# NeoGeo_JAMMA_OD.net
KiCad netlist of a schematic drawn in EAGLE
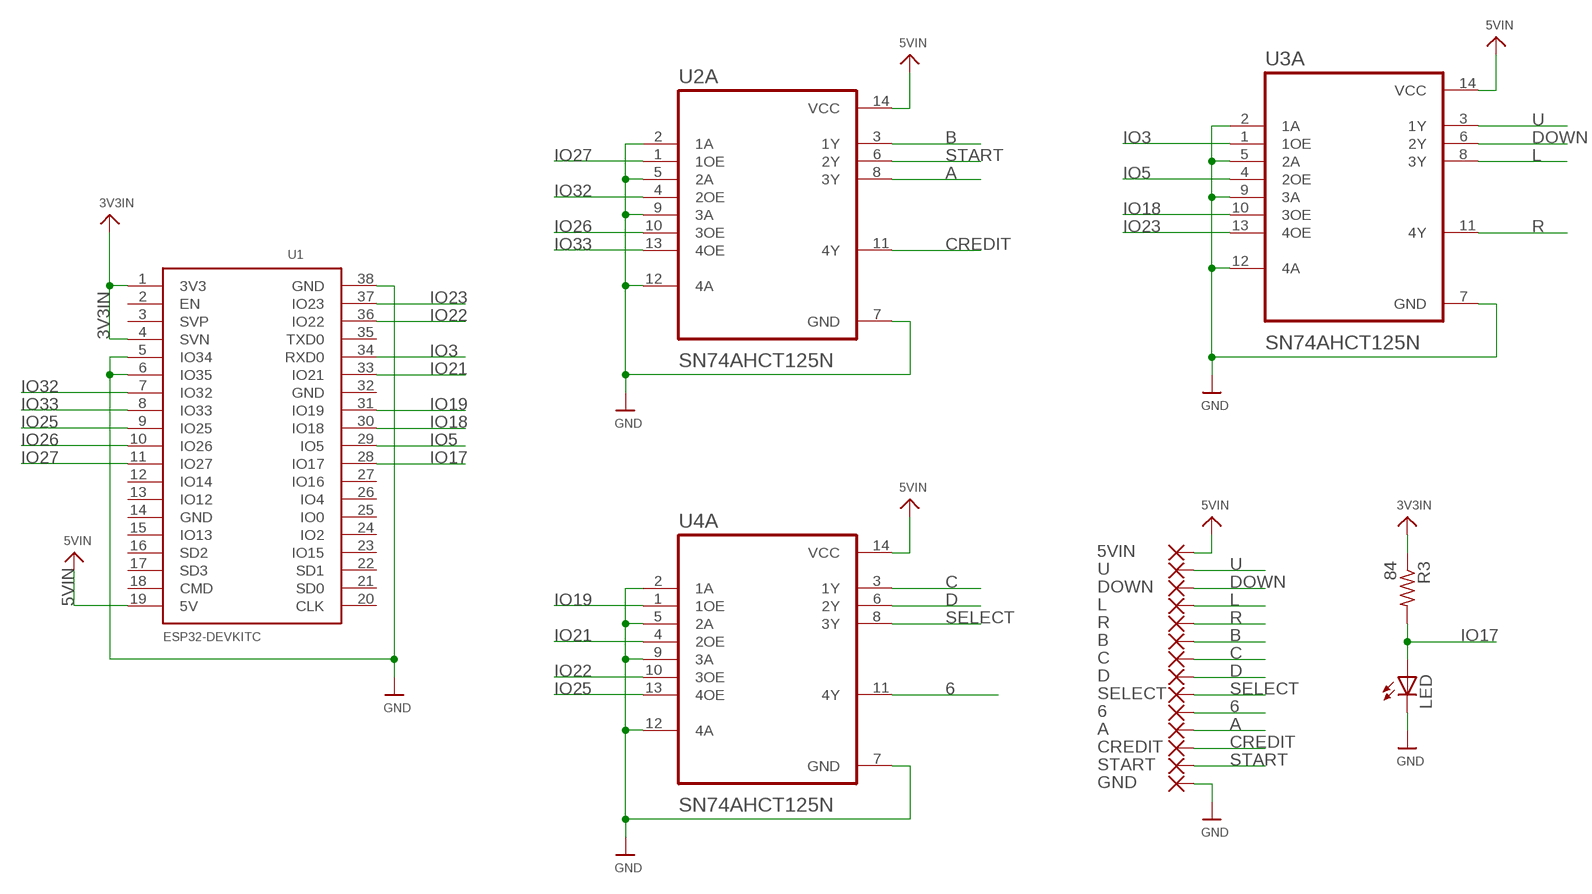
[diagram p0: schematic, sheet 1]

(export (version "E")
  (design (tool "Eeschema 10.0.6"))
  (components
    (comp (ref "5VIN")
      (value "SMD5")
      (footprint "eagle-import:SMD2,54-5,08")
      (libsource (lib "eagle-import") (part "SMD5"))
    )
    (comp (ref "6")
      (value "SMD5")
      (footprint "eagle-import:SMD2,54-5,08")
      (libsource (lib "eagle-import") (part "SMD5"))
    )
    (comp (ref "A")
      (value "SMD5")
      (footprint "eagle-import:SMD2,54-5,08")
      (libsource (lib "eagle-import") (part "SMD5"))
    )
    (comp (ref "B")
      (value "SMD5")
      (footprint "eagle-import:SMD2,54-5,08")
      (libsource (lib "eagle-import") (part "SMD5"))
    )
    (comp (ref "C")
      (value "SMD5")
      (footprint "eagle-import:SMD2,54-5,08")
      (libsource (lib "eagle-import") (part "SMD5"))
    )
    (comp (ref "CREDIT")
      (value "SMD5")
      (footprint "eagle-import:SMD2,54-5,08")
      (libsource (lib "eagle-import") (part "SMD5"))
    )
    (comp (ref "D")
      (value "SMD5")
      (footprint "eagle-import:SMD2,54-5,08")
      (libsource (lib "eagle-import") (part "SMD5"))
    )
    (comp (ref "DOWN")
      (value "SMD5")
      (footprint "eagle-import:SMD2,54-5,08")
      (libsource (lib "eagle-import") (part "SMD5"))
    )
    (comp (ref "GND")
      (value "SMD5")
      (footprint "eagle-import:SMD2,54-5,08")
      (libsource (lib "eagle-import") (part "SMD5"))
    )
    (comp (ref "L")
      (value "SMD5")
      (footprint "eagle-import:SMD2,54-5,08")
      (libsource (lib "eagle-import") (part "SMD5"))
    )
    (comp (ref "LED")
      (value "LEDCHIPLED_1206")
      (footprint "eagle-import:CHIPLED_1206")
      (libsource (lib "eagle-import") (part "LEDCHIPLED_1206"))
    )
    (comp (ref "R")
      (value "SMD5")
      (footprint "eagle-import:SMD2,54-5,08")
      (libsource (lib "eagle-import") (part "SMD5"))
    )
    (comp (ref "R3")
      (value "84")
      (footprint "eagle-import:R1206")
      (libsource (lib "eagle-import") (part "R-US_R1206"))
    )
    (comp (ref "SELECT")
      (value "SMD5")
      (footprint "eagle-import:SMD2,54-5,08")
      (libsource (lib "eagle-import") (part "SMD5"))
    )
    (comp (ref "START")
      (value "SMD5")
      (footprint "eagle-import:SMD2,54-5,08")
      (libsource (lib "eagle-import") (part "SMD5"))
    )
    (comp (ref "U")
      (value "SMD5")
      (footprint "eagle-import:SMD2,54-5,08")
      (libsource (lib "eagle-import") (part "SMD5"))
    )
    (comp (ref "U1")
      (value "ESP32DEVKITC")
      (footprint "eagle-import:ESP32-DEVKITC")
      (libsource (lib "eagle-import") (part "ESP32DEVKITC"))
    )
    (comp (ref "U2A")
      (value "SN74AHCT125N")
      (footprint "eagle-import:DIP794W45P254L1969H508Q14")
      (fields (field (name "MF") "Texas Instruments"))
      (libsource (lib "eagle-import") (part "SN74AHCT125N"))
    )
    (comp (ref "U3A")
      (value "SN74AHCT125N")
      (footprint "eagle-import:DIP794W45P254L1969H508Q14")
      (fields (field (name "MF") "Texas Instruments"))
      (libsource (lib "eagle-import") (part "SN74AHCT125N"))
    )
    (comp (ref "U4A")
      (value "SN74AHCT125N")
      (footprint "eagle-import:DIP794W45P254L1969H508Q14")
      (fields (field (name "MF") "Texas Instruments"))
      (libsource (lib "eagle-import") (part "SN74AHCT125N"))
    )
  )
  (nets
    (net (code "1") (name "/6") (class "Default")
      (node (ref "6") (pin "1") (pinfunction "P_1") (pintype "passive"))
      (node (ref "U4A") (pin "11") (pinfunction "4Y_11") (pintype "output"))
    )
    (net (code "2") (name "/A") (class "Default")
      (node (ref "A") (pin "1") (pinfunction "P_1") (pintype "passive"))
      (node (ref "U2A") (pin "8") (pinfunction "3Y_8") (pintype "output"))
    )
    (net (code "3") (name "/B") (class "Default")
      (node (ref "B") (pin "1") (pinfunction "P_1") (pintype "passive"))
      (node (ref "U2A") (pin "3") (pinfunction "1Y_3") (pintype "output"))
    )
    (net (code "4") (name "/C") (class "Default")
      (node (ref "C") (pin "1") (pinfunction "P_1") (pintype "passive"))
      (node (ref "U4A") (pin "3") (pinfunction "1Y_3") (pintype "output"))
    )
    (net (code "5") (name "/CREDIT") (class "Default")
      (node (ref "CREDIT") (pin "1") (pinfunction "P_1") (pintype "passive"))
      (node (ref "U2A") (pin "11") (pinfunction "4Y_11") (pintype "output"))
    )
    (net (code "6") (name "/D") (class "Default")
      (node (ref "D") (pin "1") (pinfunction "P_1") (pintype "passive"))
      (node (ref "U4A") (pin "6") (pinfunction "2Y_6") (pintype "output"))
    )
    (net (code "7") (name "/DOWN") (class "Default")
      (node (ref "DOWN") (pin "1") (pinfunction "P_1") (pintype "passive"))
      (node (ref "U3A") (pin "6") (pinfunction "2Y_6") (pintype "output"))
    )
    (net (code "8") (name "/IO3") (class "Default")
      (node (ref "U1") (pin "34") (pinfunction "RXD0_34") (pintype "bidirectional"))
      (node (ref "U3A") (pin "1") (pinfunction "1OE_1") (pintype "input"))
    )
    (net (code "9") (name "/IO5") (class "Default")
      (node (ref "U1") (pin "29") (pinfunction "IO5_29") (pintype "bidirectional"))
      (node (ref "U3A") (pin "4") (pinfunction "2OE_4") (pintype "input"))
    )
    (net (code "10") (name "/IO17") (class "Default")
      (node (ref "LED") (pin "A") (pinfunction "A_A") (pintype "passive"))
      (node (ref "R3") (pin "2") (pinfunction "2_2") (pintype "passive"))
      (node (ref "U1") (pin "28") (pinfunction "IO17_28") (pintype "bidirectional"))
    )
    (net (code "11") (name "/IO18") (class "Default")
      (node (ref "U1") (pin "30") (pinfunction "IO18_30") (pintype "bidirectional"))
      (node (ref "U3A") (pin "10") (pinfunction "3OE_10") (pintype "input"))
    )
    (net (code "12") (name "/IO19") (class "Default")
      (node (ref "U1") (pin "31") (pinfunction "IO19_31") (pintype "bidirectional"))
      (node (ref "U4A") (pin "1") (pinfunction "1OE_1") (pintype "input"))
    )
    (net (code "13") (name "/IO21") (class "Default")
      (node (ref "U1") (pin "33") (pinfunction "IO21_33") (pintype "bidirectional"))
      (node (ref "U4A") (pin "4") (pinfunction "2OE_4") (pintype "input"))
    )
    (net (code "14") (name "/IO22") (class "Default")
      (node (ref "U1") (pin "36") (pinfunction "IO22_36") (pintype "bidirectional"))
      (node (ref "U4A") (pin "10") (pinfunction "3OE_10") (pintype "input"))
    )
    (net (code "15") (name "/IO23") (class "Default")
      (node (ref "U1") (pin "37") (pinfunction "IO23_37") (pintype "bidirectional"))
      (node (ref "U3A") (pin "13") (pinfunction "4OE_13") (pintype "input"))
    )
    (net (code "16") (name "/IO25") (class "Default")
      (node (ref "U1") (pin "9") (pinfunction "IO25_9") (pintype "bidirectional"))
      (node (ref "U4A") (pin "13") (pinfunction "4OE_13") (pintype "input"))
    )
    (net (code "17") (name "/IO26") (class "Default")
      (node (ref "U1") (pin "10") (pinfunction "IO26_10") (pintype "bidirectional"))
      (node (ref "U2A") (pin "10") (pinfunction "3OE_10") (pintype "input"))
    )
    (net (code "18") (name "/IO27") (class "Default")
      (node (ref "U1") (pin "11") (pinfunction "IO27_11") (pintype "bidirectional"))
      (node (ref "U2A") (pin "1") (pinfunction "1OE_1") (pintype "input"))
    )
    (net (code "19") (name "/IO32") (class "Default")
      (node (ref "U1") (pin "7") (pinfunction "IO32_7") (pintype "bidirectional"))
      (node (ref "U2A") (pin "4") (pinfunction "2OE_4") (pintype "input"))
    )
    (net (code "20") (name "/IO33") (class "Default")
      (node (ref "U1") (pin "8") (pinfunction "IO33_8") (pintype "bidirectional"))
      (node (ref "U2A") (pin "13") (pinfunction "4OE_13") (pintype "input"))
    )
    (net (code "21") (name "/L") (class "Default")
      (node (ref "L") (pin "1") (pinfunction "P_1") (pintype "passive"))
      (node (ref "U3A") (pin "8") (pinfunction "3Y_8") (pintype "output"))
    )
    (net (code "22") (name "/R") (class "Default")
      (node (ref "R") (pin "1") (pinfunction "P_1") (pintype "passive"))
      (node (ref "U3A") (pin "11") (pinfunction "4Y_11") (pintype "output"))
    )
    (net (code "23") (name "/SELECT") (class "Default")
      (node (ref "SELECT") (pin "1") (pinfunction "P_1") (pintype "passive"))
      (node (ref "U4A") (pin "8") (pinfunction "3Y_8") (pintype "output"))
    )
    (net (code "24") (name "/START") (class "Default")
      (node (ref "START") (pin "1") (pinfunction "P_1") (pintype "passive"))
      (node (ref "U2A") (pin "6") (pinfunction "2Y_6") (pintype "output"))
    )
    (net (code "25") (name "/U") (class "Default")
      (node (ref "U") (pin "1") (pinfunction "P_1") (pintype "passive"))
      (node (ref "U3A") (pin "3") (pinfunction "1Y_3") (pintype "output"))
    )
    (net (code "26") (name "3V3IN") (class "Default")
      (node (ref "R3") (pin "1") (pinfunction "1_1") (pintype "passive"))
      (node (ref "U1") (pin "1") (pinfunction "3V3_1") (pintype "bidirectional"))
      (node (ref "U1") (pin "4") (pinfunction "SVN_4") (pintype "bidirectional"))
    )
    (net (code "27") (name "5VIN") (class "Default")
      (node (ref "5VIN") (pin "1") (pinfunction "P_1") (pintype "passive"))
      (node (ref "U1") (pin "19") (pinfunction "5V_19") (pintype "bidirectional"))
      (node (ref "U2A") (pin "14") (pinfunction "VCC_14") (pintype "power_in"))
      (node (ref "U3A") (pin "14") (pinfunction "VCC_14") (pintype "power_in"))
      (node (ref "U4A") (pin "14") (pinfunction "VCC_14") (pintype "power_in"))
    )
    (net (code "28") (name "GND") (class "Default")
      (node (ref "GND") (pin "1") (pinfunction "P_1") (pintype "passive"))
      (node (ref "LED") (pin "C") (pinfunction "C_C") (pintype "passive"))
      (node (ref "U1") (pin "38") (pinfunction "GND_38") (pintype "bidirectional"))
      (node (ref "U1") (pin "5") (pinfunction "IO34_5") (pintype "bidirectional"))
      (node (ref "U1") (pin "6") (pinfunction "IO35_6") (pintype "bidirectional"))
      (node (ref "U2A") (pin "12") (pinfunction "4A_12") (pintype "bidirectional"))
      (node (ref "U2A") (pin "2") (pinfunction "1A_2") (pintype "input"))
      (node (ref "U2A") (pin "5") (pinfunction "2A_5") (pintype "input"))
      (node (ref "U2A") (pin "7") (pinfunction "GND_7") (pintype "power_in"))
      (node (ref "U2A") (pin "9") (pinfunction "3A_9") (pintype "input"))
      (node (ref "U3A") (pin "12") (pinfunction "4A_12") (pintype "bidirectional"))
      (node (ref "U3A") (pin "2") (pinfunction "1A_2") (pintype "input"))
      (node (ref "U3A") (pin "5") (pinfunction "2A_5") (pintype "input"))
      (node (ref "U3A") (pin "7") (pinfunction "GND_7") (pintype "power_in"))
      (node (ref "U3A") (pin "9") (pinfunction "3A_9") (pintype "input"))
      (node (ref "U4A") (pin "12") (pinfunction "4A_12") (pintype "bidirectional"))
      (node (ref "U4A") (pin "2") (pinfunction "1A_2") (pintype "input"))
      (node (ref "U4A") (pin "5") (pinfunction "2A_5") (pintype "input"))
      (node (ref "U4A") (pin "7") (pinfunction "GND_7") (pintype "power_in"))
      (node (ref "U4A") (pin "9") (pinfunction "3A_9") (pintype "input"))
    )
    (net (code "29") (name "unconnected-(U1-CLK-Pad20)") (class "Default")
      (node (ref "U1") (pin "20") (pinfunction "CLK_20") (pintype "bidirectional"))
    )
    (net (code "30") (name "unconnected-(U1-CMD-Pad18)") (class "Default")
      (node (ref "U1") (pin "18") (pinfunction "CMD_18") (pintype "bidirectional"))
    )
    (net (code "31") (name "unconnected-(U1-EN-Pad2)") (class "Default")
      (node (ref "U1") (pin "2") (pinfunction "EN_2") (pintype "bidirectional"))
    )
    (net (code "32") (name "unconnected-(U1-GND-Pad14)") (class "Default")
      (node (ref "U1") (pin "14") (pinfunction "GND_14") (pintype "bidirectional"))
    )
    (net (code "33") (name "unconnected-(U1-GND-Pad32)") (class "Default")
      (node (ref "U1") (pin "32") (pinfunction "GND_32") (pintype "bidirectional"))
    )
    (net (code "34") (name "unconnected-(U1-IO0-Pad25)") (class "Default")
      (node (ref "U1") (pin "25") (pinfunction "IO0_25") (pintype "bidirectional"))
    )
    (net (code "35") (name "unconnected-(U1-IO2-Pad24)") (class "Default")
      (node (ref "U1") (pin "24") (pinfunction "IO2_24") (pintype "bidirectional"))
    )
    (net (code "36") (name "unconnected-(U1-IO4-Pad26)") (class "Default")
      (node (ref "U1") (pin "26") (pinfunction "IO4_26") (pintype "bidirectional"))
    )
    (net (code "37") (name "unconnected-(U1-IO12-Pad13)") (class "Default")
      (node (ref "U1") (pin "13") (pinfunction "IO12_13") (pintype "bidirectional"))
    )
    (net (code "38") (name "unconnected-(U1-IO13-Pad15)") (class "Default")
      (node (ref "U1") (pin "15") (pinfunction "IO13_15") (pintype "bidirectional"))
    )
    (net (code "39") (name "unconnected-(U1-IO14-Pad12)") (class "Default")
      (node (ref "U1") (pin "12") (pinfunction "IO14_12") (pintype "bidirectional"))
    )
    (net (code "40") (name "unconnected-(U1-IO15-Pad23)") (class "Default")
      (node (ref "U1") (pin "23") (pinfunction "IO15_23") (pintype "bidirectional"))
    )
    (net (code "41") (name "unconnected-(U1-IO16-Pad27)") (class "Default")
      (node (ref "U1") (pin "27") (pinfunction "IO16_27") (pintype "bidirectional"))
    )
    (net (code "42") (name "unconnected-(U1-SD0-Pad21)") (class "Default")
      (node (ref "U1") (pin "21") (pinfunction "SD0_21") (pintype "bidirectional"))
    )
    (net (code "43") (name "unconnected-(U1-SD1-Pad22)") (class "Default")
      (node (ref "U1") (pin "22") (pinfunction "SD1_22") (pintype "bidirectional"))
    )
    (net (code "44") (name "unconnected-(U1-SD2-Pad16)") (class "Default")
      (node (ref "U1") (pin "16") (pinfunction "SD2_16") (pintype "bidirectional"))
    )
    (net (code "45") (name "unconnected-(U1-SD3-Pad17)") (class "Default")
      (node (ref "U1") (pin "17") (pinfunction "SD3_17") (pintype "bidirectional"))
    )
    (net (code "46") (name "unconnected-(U1-SVP-Pad3)") (class "Default")
      (node (ref "U1") (pin "3") (pinfunction "SVP_3") (pintype "bidirectional"))
    )
    (net (code "47") (name "unconnected-(U1-TXD0-Pad35)") (class "Default")
      (node (ref "U1") (pin "35") (pinfunction "TXD0_35") (pintype "bidirectional"))
    )
  )
)
